# FlexEMG_v0r0_SF2-POWER.net
KiCad netlist of a schematic drawn in Altium Designer
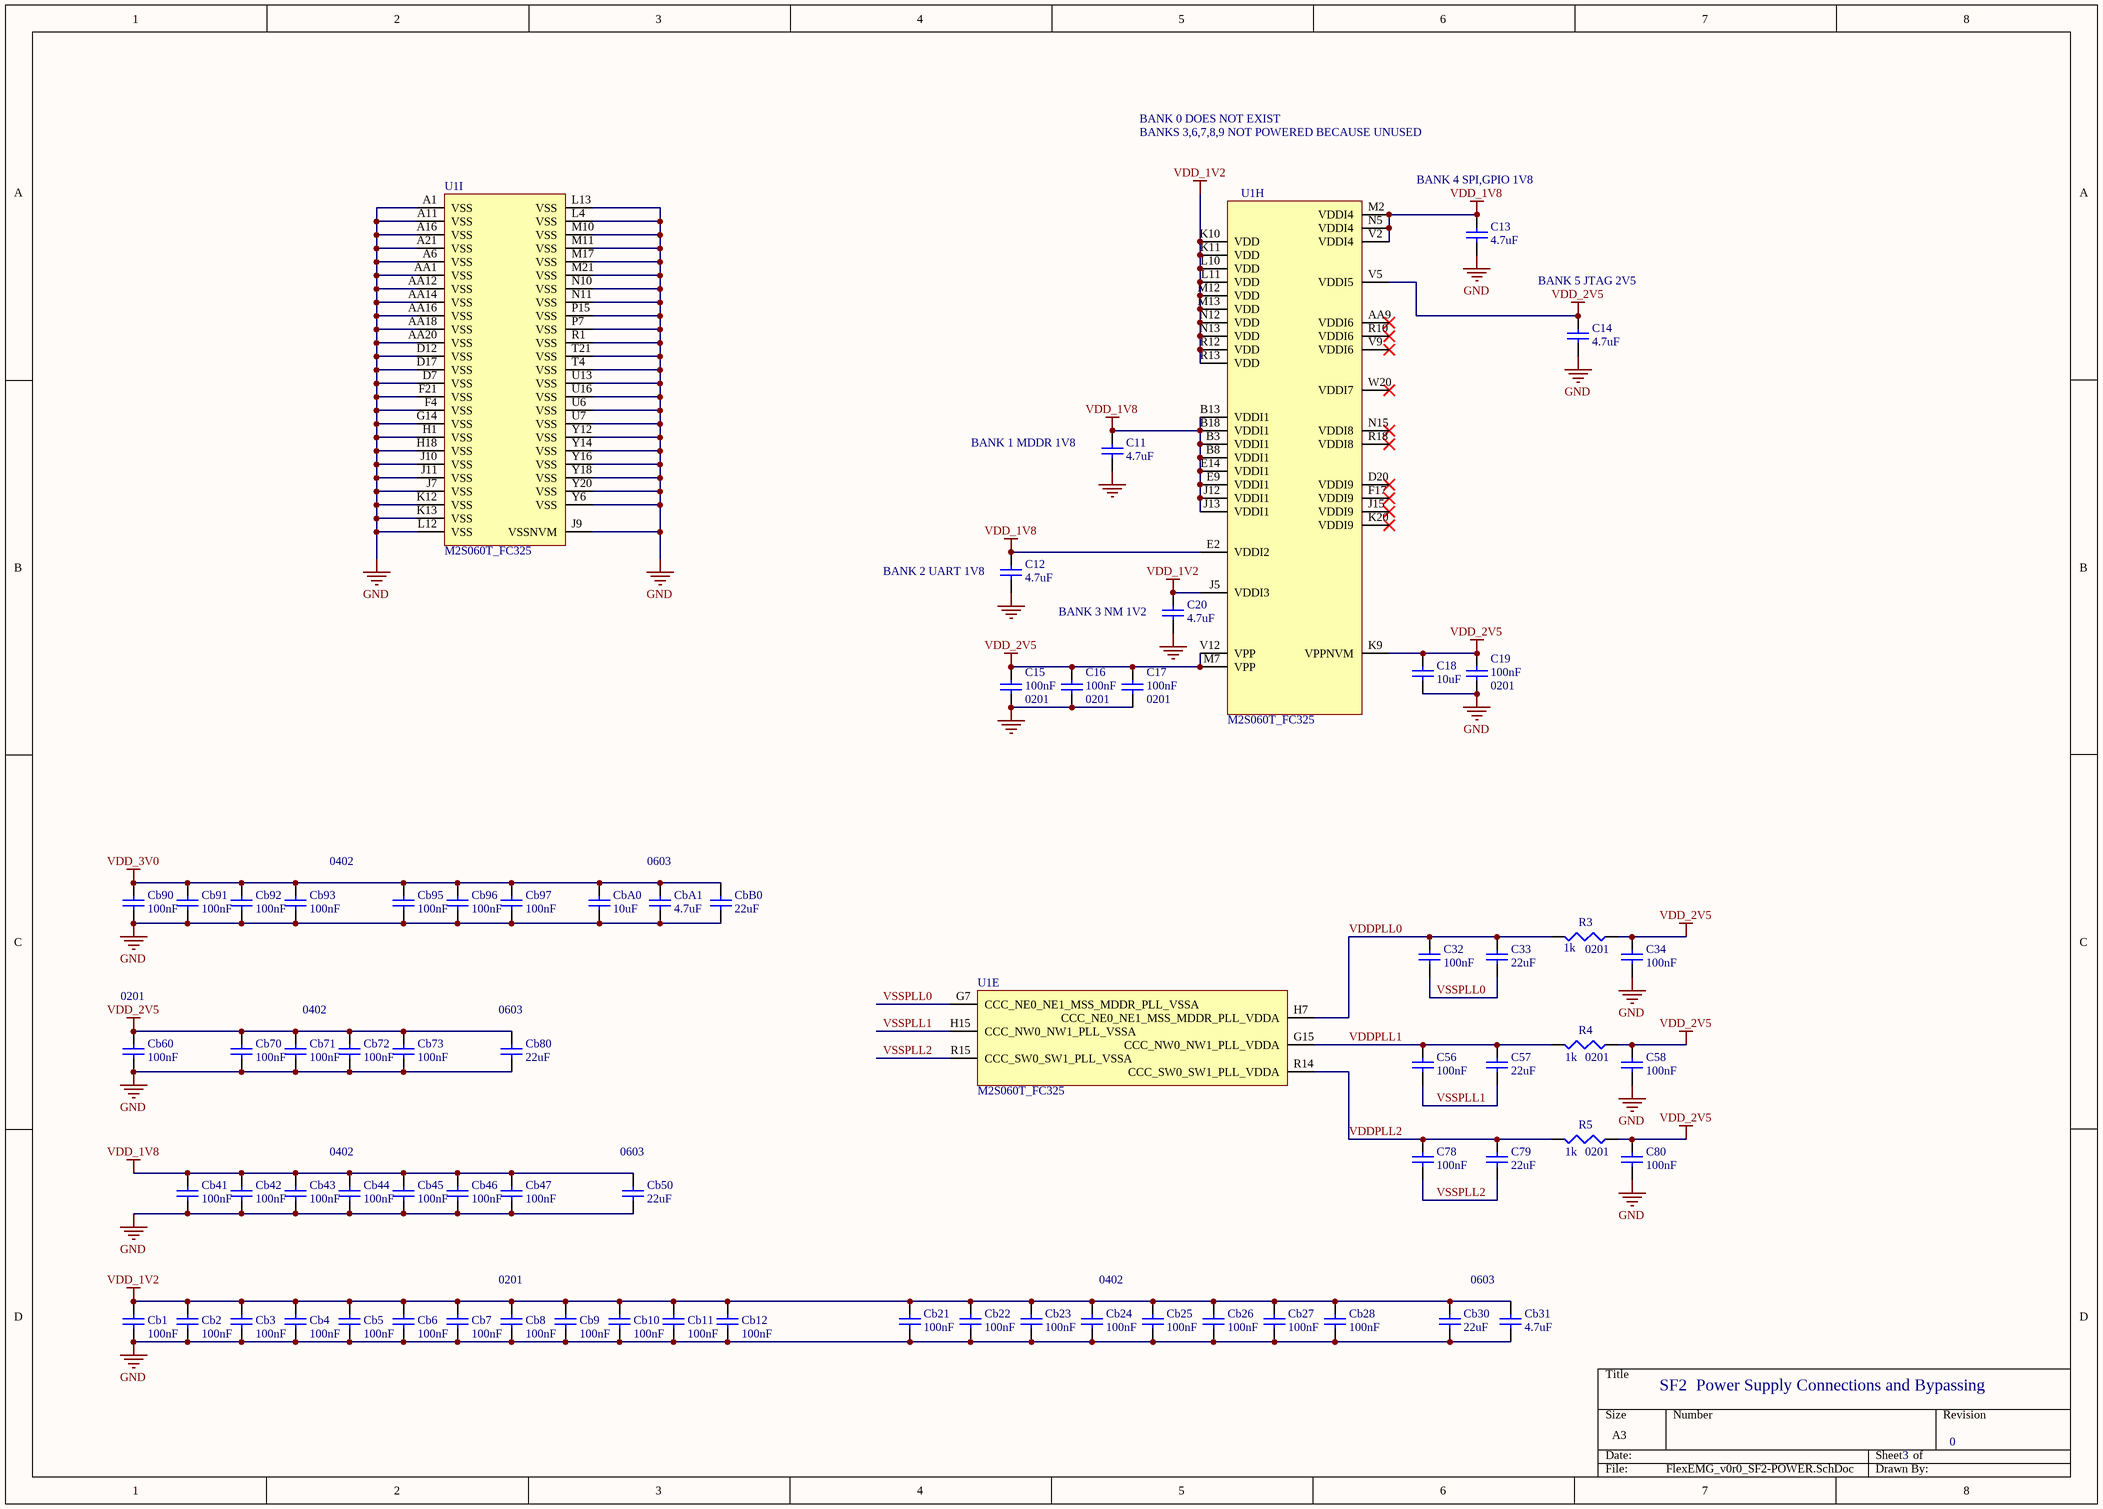
[diagram p0: FlexEMG_v0r0_SF2-POWER.SchDoc]

(export (version "E")
  (design (tool "Eeschema 10.0.6"))
  (components
    (comp (ref "C11")
      (value "4.7uF")
      (footprint "c0603-Murata-GR")
      (description "CAP CER 4.7UF 35V X5R 0603")
      (fields (field (name "MANUFACTURER") "Murata") (field (name "Comment") "GRM188R6YA475KE15D"))
      (libsource (lib "Custom") (part "Cap"))
    )
    (comp (ref "C12")
      (value "4.7uF")
      (footprint "c0603-Murata-GR")
      (description "CAP CER 4.7UF 35V X5R 0603")
      (fields (field (name "MANUFACTURER") "Murata") (field (name "Comment") "GRM188R6YA475KE15D"))
      (libsource (lib "Custom") (part "Cap"))
    )
    (comp (ref "C13")
      (value "4.7uF")
      (footprint "c0603-Murata-GR")
      (description "CAP CER 4.7UF 35V X5R 0603")
      (fields (field (name "MANUFACTURER") "Murata") (field (name "Comment") "GRM188R6YA475KE15D"))
      (libsource (lib "Custom") (part "Cap"))
    )
    (comp (ref "C14")
      (value "4.7uF")
      (footprint "c0603-Murata-GR")
      (description "CAP CER 4.7UF 35V X5R 0603")
      (fields (field (name "MANUFACTURER") "Murata") (field (name "Comment") "GRM188R6YA475KE15D"))
      (libsource (lib "Custom") (part "Cap"))
    )
    (comp (ref "C15")
      (value "100nF")
      (footprint "c0201-Murata-GR")
      (description "CAP CER 0.1UF 16V X7S 0201")
      (fields
        (field (name "MANUFACTURER") "Murata")
        (field (name "PACKAGE") "0201")
        (field (name "Comment") "GRM033R6YA104KE14D")
      )
      (libsource (lib "Custom") (part "Cap"))
    )
    (comp (ref "C16")
      (value "100nF")
      (footprint "c0201-Murata-GR")
      (description "CAP CER 0.1UF 16V X7S 0201")
      (fields
        (field (name "MANUFACTURER") "Murata")
        (field (name "PACKAGE") "0201")
        (field (name "Comment") "GRM033R6YA104KE14D")
      )
      (libsource (lib "Custom") (part "Cap"))
    )
    (comp (ref "C17")
      (value "100nF")
      (footprint "c0201-Murata-GR")
      (description "CAP CER 0.1UF 16V X7S 0201")
      (fields
        (field (name "MANUFACTURER") "Murata")
        (field (name "PACKAGE") "0201")
        (field (name "Comment") "GRM033R6YA104KE14D")
      )
      (libsource (lib "Custom") (part "Cap"))
    )
    (comp (ref "C18")
      (value "10uF")
      (footprint "c0603-Murata-GR")
      (description "CAP CER 10UF 25V X5R 0603 20%")
      (fields (field (name "MANUFACTURER") "Murata") (field (name "Comment") "GRM188R61E106MA73D"))
      (libsource (lib "Custom") (part "Cap"))
    )
    (comp (ref "C19")
      (value "100nF")
      (footprint "c0201-Murata-GR")
      (description "CAP CER 0.1UF 16V X7S 0201")
      (fields
        (field (name "MANUFACTURER") "Murata")
        (field (name "PACKAGE") "0201")
        (field (name "Comment") "GRM033R6YA104KE14D")
      )
      (libsource (lib "Custom") (part "Cap"))
    )
    (comp (ref "C20")
      (value "4.7uF")
      (footprint "c0603-Murata-GR")
      (description "CAP CER 4.7UF 35V X5R 0603")
      (fields (field (name "MANUFACTURER") "Murata") (field (name "Comment") "GRM188R6YA475KE15D"))
      (libsource (lib "Custom") (part "Cap"))
    )
    (comp (ref "C32")
      (value "100nF")
      (footprint "c0402-Murata-GR")
      (description "CAP CER 0.1UF 50V X5R 0402")
      (fields (field (name "MANUFACTURER") "Murata") (field (name "Comment") "GRM155R61H104KE19D"))
      (libsource (lib "Custom") (part "Cap"))
    )
    (comp (ref "C33")
      (value "22uF")
      (footprint "c0603-Murata-GR")
      (description "CAP CER 22UF 10V X5R 0603")
      (fields (field (name "MANUFACTURER") "Murata") (field (name "Comment") "GRM187R61A226ME15D"))
      (libsource (lib "Custom") (part "Cap"))
    )
    (comp (ref "C34")
      (value "100nF")
      (footprint "c0402-Murata-GR")
      (description "CAP CER 0.1UF 50V X5R 0402")
      (fields (field (name "MANUFACTURER") "Murata") (field (name "Comment") "GRM155R61H104KE19D"))
      (libsource (lib "Custom") (part "Cap"))
    )
    (comp (ref "C56")
      (value "100nF")
      (footprint "c0402-Murata-GR")
      (description "CAP CER 0.1UF 50V X5R 0402")
      (fields (field (name "MANUFACTURER") "Murata") (field (name "Comment") "GRM155R61H104KE19D"))
      (libsource (lib "Custom") (part "Cap"))
    )
    (comp (ref "C57")
      (value "22uF")
      (footprint "c0603-Murata-GR")
      (description "CAP CER 22UF 10V X5R 0603")
      (fields (field (name "MANUFACTURER") "Murata") (field (name "Comment") "GRM187R61A226ME15D"))
      (libsource (lib "Custom") (part "Cap"))
    )
    (comp (ref "C58")
      (value "100nF")
      (footprint "c0402-Murata-GR")
      (description "CAP CER 0.1UF 50V X5R 0402")
      (fields (field (name "MANUFACTURER") "Murata") (field (name "Comment") "GRM155R61H104KE19D"))
      (libsource (lib "Custom") (part "Cap"))
    )
    (comp (ref "C78")
      (value "100nF")
      (footprint "c0402-Murata-GR")
      (description "CAP CER 0.1UF 50V X5R 0402")
      (fields (field (name "MANUFACTURER") "Murata") (field (name "Comment") "GRM155R61H104KE19D"))
      (libsource (lib "Custom") (part "Cap"))
    )
    (comp (ref "C79")
      (value "22uF")
      (footprint "c0603-Murata-GR")
      (description "CAP CER 22UF 10V X5R 0603")
      (fields (field (name "MANUFACTURER") "Murata") (field (name "Comment") "GRM187R61A226ME15D"))
      (libsource (lib "Custom") (part "Cap"))
    )
    (comp (ref "C80")
      (value "100nF")
      (footprint "c0402-Murata-GR")
      (description "CAP CER 0.1UF 50V X5R 0402")
      (fields (field (name "MANUFACTURER") "Murata") (field (name "Comment") "GRM155R61H104KE19D"))
      (libsource (lib "Custom") (part "Cap"))
    )
    (comp (ref "Cb1")
      (value "100nF")
      (footprint "c0201-Murata-GR")
      (description "CAP CER 0.1UF 16V X7S 0201")
      (fields (field (name "MANUFACTURER") "Murata") (field (name "Comment") "GRM033R6YA104KE14D"))
      (libsource (lib "Custom") (part "Cap"))
    )
    (comp (ref "Cb2")
      (value "100nF")
      (footprint "c0201-Murata-GR")
      (description "CAP CER 0.1UF 16V X7S 0201")
      (fields (field (name "MANUFACTURER") "Murata") (field (name "Comment") "GRM033R6YA104KE14D"))
      (libsource (lib "Custom") (part "Cap"))
    )
    (comp (ref "Cb3")
      (value "100nF")
      (footprint "c0201-Murata-GR")
      (description "CAP CER 0.1UF 16V X7S 0201")
      (fields (field (name "MANUFACTURER") "Murata") (field (name "Comment") "GRM033R6YA104KE14D"))
      (libsource (lib "Custom") (part "Cap"))
    )
    (comp (ref "Cb4")
      (value "100nF")
      (footprint "c0201-Murata-GR")
      (description "CAP CER 0.1UF 16V X7S 0201")
      (fields (field (name "MANUFACTURER") "Murata") (field (name "Comment") "GRM033R6YA104KE14D"))
      (libsource (lib "Custom") (part "Cap"))
    )
    (comp (ref "Cb5")
      (value "100nF")
      (footprint "c0201-Murata-GR")
      (description "CAP CER 0.1UF 16V X7S 0201")
      (fields (field (name "MANUFACTURER") "Murata") (field (name "Comment") "GRM033R6YA104KE14D"))
      (libsource (lib "Custom") (part "Cap"))
    )
    (comp (ref "Cb6")
      (value "100nF")
      (footprint "c0201-Murata-GR")
      (description "CAP CER 0.1UF 16V X7S 0201")
      (fields (field (name "MANUFACTURER") "Murata") (field (name "Comment") "GRM033R6YA104KE14D"))
      (libsource (lib "Custom") (part "Cap"))
    )
    (comp (ref "Cb7")
      (value "100nF")
      (footprint "c0201-Murata-GR")
      (description "CAP CER 0.1UF 16V X7S 0201")
      (fields (field (name "MANUFACTURER") "Murata") (field (name "Comment") "GRM033R6YA104KE14D"))
      (libsource (lib "Custom") (part "Cap"))
    )
    (comp (ref "Cb8")
      (value "100nF")
      (footprint "c0201-Murata-GR")
      (description "CAP CER 0.1UF 16V X7S 0201")
      (fields (field (name "MANUFACTURER") "Murata") (field (name "Comment") "GRM033R6YA104KE14D"))
      (libsource (lib "Custom") (part "Cap"))
    )
    (comp (ref "Cb9")
      (value "100nF")
      (footprint "c0201-Murata-GR")
      (description "CAP CER 0.1UF 16V X7S 0201")
      (fields (field (name "MANUFACTURER") "Murata") (field (name "Comment") "GRM033R6YA104KE14D"))
      (libsource (lib "Custom") (part "Cap"))
    )
    (comp (ref "Cb10")
      (value "100nF")
      (footprint "c0201-Murata-GR")
      (description "CAP CER 0.1UF 16V X7S 0201")
      (fields (field (name "MANUFACTURER") "Murata") (field (name "Comment") "GRM033R6YA104KE14D"))
      (libsource (lib "Custom") (part "Cap"))
    )
    (comp (ref "Cb11")
      (value "100nF")
      (footprint "c0201-Murata-GR")
      (description "CAP CER 0.1UF 16V X7S 0201")
      (fields (field (name "MANUFACTURER") "Murata") (field (name "Comment") "GRM033R6YA104KE14D"))
      (libsource (lib "Custom") (part "Cap"))
    )
    (comp (ref "Cb12")
      (value "100nF")
      (footprint "c0201-Murata-GR")
      (description "CAP CER 0.1UF 16V X7S 0201")
      (fields (field (name "MANUFACTURER") "Murata") (field (name "Comment") "GRM033R6YA104KE14D"))
      (libsource (lib "Custom") (part "Cap"))
    )
    (comp (ref "Cb21")
      (value "100nF")
      (footprint "c0402-Murata-GR")
      (description "CAP CER 0.1UF 50V X5R 0402")
      (fields (field (name "MANUFACTURER") "Murata") (field (name "Comment") "GRM155R61H104KE19D"))
      (libsource (lib "Custom") (part "Cap"))
    )
    (comp (ref "Cb22")
      (value "100nF")
      (footprint "c0402-Murata-GR")
      (description "CAP CER 0.1UF 50V X5R 0402")
      (fields (field (name "MANUFACTURER") "Murata") (field (name "Comment") "GRM155R61H104KE19D"))
      (libsource (lib "Custom") (part "Cap"))
    )
    (comp (ref "Cb23")
      (value "100nF")
      (footprint "c0402-Murata-GR")
      (description "CAP CER 0.1UF 50V X5R 0402")
      (fields (field (name "MANUFACTURER") "Murata") (field (name "Comment") "GRM155R61H104KE19D"))
      (libsource (lib "Custom") (part "Cap"))
    )
    (comp (ref "Cb24")
      (value "100nF")
      (footprint "c0402-Murata-GR")
      (description "CAP CER 0.1UF 50V X5R 0402")
      (fields (field (name "MANUFACTURER") "Murata") (field (name "Comment") "GRM155R61H104KE19D"))
      (libsource (lib "Custom") (part "Cap"))
    )
    (comp (ref "Cb25")
      (value "100nF")
      (footprint "c0402-Murata-GR")
      (description "CAP CER 0.1UF 50V X5R 0402")
      (fields (field (name "MANUFACTURER") "Murata") (field (name "Comment") "GRM155R61H104KE19D"))
      (libsource (lib "Custom") (part "Cap"))
    )
    (comp (ref "Cb26")
      (value "100nF")
      (footprint "c0402-Murata-GR")
      (description "CAP CER 0.1UF 50V X5R 0402")
      (fields (field (name "MANUFACTURER") "Murata") (field (name "Comment") "GRM155R61H104KE19D"))
      (libsource (lib "Custom") (part "Cap"))
    )
    (comp (ref "Cb27")
      (value "100nF")
      (footprint "c0402-Murata-GR")
      (description "CAP CER 0.1UF 50V X5R 0402")
      (fields (field (name "MANUFACTURER") "Murata") (field (name "Comment") "GRM155R61H104KE19D"))
      (libsource (lib "Custom") (part "Cap"))
    )
    (comp (ref "Cb28")
      (value "100nF")
      (footprint "c0402-Murata-GR")
      (description "CAP CER 0.1UF 50V X5R 0402")
      (fields (field (name "MANUFACTURER") "Murata") (field (name "Comment") "GRM155R61H104KE19D"))
      (libsource (lib "Custom") (part "Cap"))
    )
    (comp (ref "Cb30")
      (value "22uF")
      (footprint "c0603-Murata-GR")
      (description "CAP CER 22UF 10V X5R 0603")
      (fields (field (name "MANUFACTURER") "Murata") (field (name "Comment") "GRM187R61A226ME15D"))
      (libsource (lib "Custom") (part "Cap"))
    )
    (comp (ref "Cb31")
      (value "4.7uF")
      (footprint "c0603-Murata-GR")
      (description "CAP CER 4.7UF 35V X5R 0603")
      (fields (field (name "MANUFACTURER") "Murata") (field (name "Comment") "GRM188R6YA475KE15D"))
      (libsource (lib "Custom") (part "Cap"))
    )
    (comp (ref "Cb41")
      (value "100nF")
      (footprint "c0402-Murata-GR")
      (description "CAP CER 0.1UF 50V X5R 0402")
      (fields (field (name "MANUFACTURER") "Murata") (field (name "Comment") "GRM155R61H104KE19D"))
      (libsource (lib "Custom") (part "Cap"))
    )
    (comp (ref "Cb42")
      (value "100nF")
      (footprint "c0402-Murata-GR")
      (description "CAP CER 0.1UF 50V X5R 0402")
      (fields (field (name "MANUFACTURER") "Murata") (field (name "Comment") "GRM155R61H104KE19D"))
      (libsource (lib "Custom") (part "Cap"))
    )
    (comp (ref "Cb43")
      (value "100nF")
      (footprint "c0402-Murata-GR")
      (description "CAP CER 0.1UF 50V X5R 0402")
      (fields (field (name "MANUFACTURER") "Murata") (field (name "Comment") "GRM155R61H104KE19D"))
      (libsource (lib "Custom") (part "Cap"))
    )
    (comp (ref "Cb44")
      (value "100nF")
      (footprint "c0402-Murata-GR")
      (description "CAP CER 0.1UF 50V X5R 0402")
      (fields (field (name "MANUFACTURER") "Murata") (field (name "Comment") "GRM155R61H104KE19D"))
      (libsource (lib "Custom") (part "Cap"))
    )
    (comp (ref "Cb45")
      (value "100nF")
      (footprint "c0402-Murata-GR")
      (description "CAP CER 0.1UF 50V X5R 0402")
      (fields (field (name "MANUFACTURER") "Murata") (field (name "Comment") "GRM155R61H104KE19D"))
      (libsource (lib "Custom") (part "Cap"))
    )
    (comp (ref "Cb46")
      (value "100nF")
      (footprint "c0402-Murata-GR")
      (description "CAP CER 0.1UF 50V X5R 0402")
      (fields (field (name "MANUFACTURER") "Murata") (field (name "Comment") "GRM155R61H104KE19D"))
      (libsource (lib "Custom") (part "Cap"))
    )
    (comp (ref "Cb47")
      (value "100nF")
      (footprint "c0402-Murata-GR")
      (description "CAP CER 0.1UF 50V X5R 0402")
      (fields (field (name "MANUFACTURER") "Murata") (field (name "Comment") "GRM155R61H104KE19D"))
      (libsource (lib "Custom") (part "Cap"))
    )
    (comp (ref "Cb50")
      (value "22uF")
      (footprint "c0603-Murata-GR")
      (description "CAP CER 22UF 10V X5R 0603")
      (fields (field (name "MANUFACTURER") "Murata") (field (name "Comment") "GRM187R61A226ME15D"))
      (libsource (lib "Custom") (part "Cap"))
    )
    (comp (ref "Cb60")
      (value "100nF")
      (footprint "c0201-Murata-GR")
      (description "CAP CER 0.1UF 16V X7S 0201")
      (fields (field (name "MANUFACTURER") "Murata") (field (name "Comment") "GRM033R6YA104KE14D"))
      (libsource (lib "Custom") (part "Cap"))
    )
    (comp (ref "Cb70")
      (value "100nF")
      (footprint "c0402-Murata-GR")
      (description "CAP CER 0.1UF 50V X5R 0402")
      (fields (field (name "MANUFACTURER") "Murata") (field (name "Comment") "GRM155R61H104KE19D"))
      (libsource (lib "Custom") (part "Cap"))
    )
    (comp (ref "Cb71")
      (value "100nF")
      (footprint "c0402-Murata-GR")
      (description "CAP CER 0.1UF 50V X5R 0402")
      (fields (field (name "MANUFACTURER") "Murata") (field (name "Comment") "GRM155R61H104KE19D"))
      (libsource (lib "Custom") (part "Cap"))
    )
    (comp (ref "Cb72")
      (value "100nF")
      (footprint "c0402-Murata-GR")
      (description "CAP CER 0.1UF 50V X5R 0402")
      (fields (field (name "MANUFACTURER") "Murata") (field (name "Comment") "GRM155R61H104KE19D"))
      (libsource (lib "Custom") (part "Cap"))
    )
    (comp (ref "Cb73")
      (value "100nF")
      (footprint "c0402-Murata-GR")
      (description "CAP CER 0.1UF 50V X5R 0402")
      (fields (field (name "MANUFACTURER") "Murata") (field (name "Comment") "GRM155R61H104KE19D"))
      (libsource (lib "Custom") (part "Cap"))
    )
    (comp (ref "Cb80")
      (value "22uF")
      (footprint "c0603-Murata-GR")
      (description "CAP CER 22UF 10V X5R 0603")
      (fields (field (name "MANUFACTURER") "Murata") (field (name "Comment") "GRM187R61A226ME15D"))
      (libsource (lib "Custom") (part "Cap"))
    )
    (comp (ref "Cb90")
      (value "100nF")
      (footprint "c0402-Murata-GR")
      (description "CAP CER 0.1UF 50V X5R 0402")
      (fields (field (name "MANUFACTURER") "Murata") (field (name "Comment") "GRM155R61H104KE19D"))
      (libsource (lib "Custom") (part "Cap"))
    )
    (comp (ref "Cb91")
      (value "100nF")
      (footprint "c0402-Murata-GR")
      (description "CAP CER 0.1UF 50V X5R 0402")
      (fields (field (name "MANUFACTURER") "Murata") (field (name "Comment") "GRM155R61H104KE19D"))
      (libsource (lib "Custom") (part "Cap"))
    )
    (comp (ref "Cb92")
      (value "100nF")
      (footprint "c0402-Murata-GR")
      (description "CAP CER 0.1UF 50V X5R 0402")
      (fields (field (name "MANUFACTURER") "Murata") (field (name "Comment") "GRM155R61H104KE19D"))
      (libsource (lib "Custom") (part "Cap"))
    )
    (comp (ref "Cb93")
      (value "100nF")
      (footprint "c0402-Murata-GR")
      (description "CAP CER 0.1UF 50V X5R 0402")
      (fields (field (name "MANUFACTURER") "Murata") (field (name "Comment") "GRM155R61H104KE19D"))
      (libsource (lib "Custom") (part "Cap"))
    )
    (comp (ref "Cb95")
      (value "100nF")
      (footprint "c0402-Murata-GR")
      (description "CAP CER 0.1UF 50V X5R 0402")
      (fields (field (name "MANUFACTURER") "Murata") (field (name "Comment") "GRM155R61H104KE19D"))
      (libsource (lib "Custom") (part "Cap"))
    )
    (comp (ref "Cb96")
      (value "100nF")
      (footprint "c0402-Murata-GR")
      (description "CAP CER 0.1UF 50V X5R 0402")
      (fields (field (name "MANUFACTURER") "Murata") (field (name "Comment") "GRM155R61H104KE19D"))
      (libsource (lib "Custom") (part "Cap"))
    )
    (comp (ref "Cb97")
      (value "100nF")
      (footprint "c0402-Murata-GR")
      (description "CAP CER 0.1UF 50V X5R 0402")
      (fields (field (name "MANUFACTURER") "Murata") (field (name "Comment") "GRM155R61H104KE19D"))
      (libsource (lib "Custom") (part "Cap"))
    )
    (comp (ref "CbA0")
      (value "10uF")
      (footprint "c0603-Murata-GR")
      (description "CAP CER 10UF 25V X5R 0603 20%")
      (fields (field (name "MANUFACTURER") "Murata") (field (name "Comment") "GRM188R61E106MA73D"))
      (libsource (lib "Custom") (part "Cap"))
    )
    (comp (ref "CbA1")
      (value "4.7uF")
      (footprint "c0603-Murata-GR")
      (description "CAP CER 4.7UF 35V X5R 0603")
      (fields (field (name "MANUFACTURER") "Murata") (field (name "Comment") "GRM188R6YA475KE15D"))
      (libsource (lib "Custom") (part "Cap"))
    )
    (comp (ref "CbB0")
      (value "22uF")
      (footprint "c0603-Murata-GR")
      (description "CAP CER 22UF 10V X5R 0603")
      (fields (field (name "MANUFACTURER") "Murata") (field (name "Comment") "GRM187R61A226ME15D"))
      (libsource (lib "Custom") (part "Cap"))
    )
    (comp (ref "R3")
      (value "1k")
      (footprint "0201_p")
      (description "RES SMD 1K OHM 1% 1/20W 0201")
      (fields
        (field (name "MANUFACTURER") "Panasonic")
        (field (name "POWER") "1/20W")
        (field (name "PACKAGE") "0201")
      )
      (libsource (lib "Custom") (part "Resistor"))
    )
    (comp (ref "R4")
      (value "1k")
      (footprint "0201_p")
      (description "RES SMD 1K OHM 1% 1/20W 0201")
      (fields
        (field (name "MANUFACTURER") "Panasonic")
        (field (name "POWER") "1/20W")
        (field (name "PACKAGE") "0201")
      )
      (libsource (lib "Custom") (part "Resistor"))
    )
    (comp (ref "R5")
      (value "1k")
      (footprint "0201_p")
      (description "RES SMD 1K OHM 1% 1/20W 0201")
      (fields
        (field (name "MANUFACTURER") "Panasonic")
        (field (name "POWER") "1/20W")
        (field (name "PACKAGE") "0201")
      )
      (libsource (lib "Custom") (part "Resistor"))
    )
    (comp (ref "U1")
      (value "M2S060T_FC325")
      (footprint "MCSM-CS-325")
      (description "SmartFusion2")
      (fields (field (name "MANUFACTURER") "Microsemi"))
      (libsource (lib "CM") (part "M2S060T_FC325"))
    )
  )
  (nets
    (net (code "1") (name "/VDDPLL0") (class "Default")
      (node (ref "C32") (pin "2") (pinfunction "2_2") (pintype "passive"))
      (node (ref "C33") (pin "2") (pinfunction "2_2") (pintype "passive"))
      (node (ref "R3") (pin "2") (pinfunction "2_2") (pintype "passive"))
      (node (ref "U1") (pin "H7") (pinfunction "CCC_NE0_NE1_MSS_MDDR_PLL_VDDA_H7") (pintype "power_in"))
    )
    (net (code "2") (name "/VDDPLL1") (class "Default")
      (node (ref "C56") (pin "2") (pinfunction "2_2") (pintype "passive"))
      (node (ref "C57") (pin "2") (pinfunction "2_2") (pintype "passive"))
      (node (ref "R4") (pin "2") (pinfunction "2_2") (pintype "passive"))
      (node (ref "U1") (pin "G15") (pinfunction "CCC_NW0_NW1_PLL_VDDA_G15") (pintype "power_in"))
    )
    (net (code "3") (name "/VDDPLL2") (class "Default")
      (node (ref "C78") (pin "2") (pinfunction "2_2") (pintype "passive"))
      (node (ref "C79") (pin "2") (pinfunction "2_2") (pintype "passive"))
      (node (ref "R5") (pin "2") (pinfunction "2_2") (pintype "passive"))
      (node (ref "U1") (pin "R14") (pinfunction "CCC_SW0_SW1_PLL_VDDA_R14") (pintype "power_in"))
    )
    (net (code "4") (name "/VSSPLL0") (class "Default")
      (node (ref "C32") (pin "1") (pinfunction "1_1") (pintype "passive"))
      (node (ref "C33") (pin "1") (pinfunction "1_1") (pintype "passive"))
      (node (ref "U1") (pin "G7") (pinfunction "CCC_NE0_NE1_MSS_MDDR_PLL_VSSA_G7") (pintype "power_in"))
    )
    (net (code "5") (name "/VSSPLL1") (class "Default")
      (node (ref "C56") (pin "1") (pinfunction "1_1") (pintype "passive"))
      (node (ref "C57") (pin "1") (pinfunction "1_1") (pintype "passive"))
      (node (ref "U1") (pin "H15") (pinfunction "CCC_NW0_NW1_PLL_VSSA_H15") (pintype "power_in"))
    )
    (net (code "6") (name "/VSSPLL2") (class "Default")
      (node (ref "C78") (pin "1") (pinfunction "1_1") (pintype "passive"))
      (node (ref "C79") (pin "1") (pinfunction "1_1") (pintype "passive"))
      (node (ref "U1") (pin "R15") (pinfunction "CCC_SW0_SW1_PLL_VSSA_R15") (pintype "power_in"))
    )
    (net (code "7") (name "GND") (class "Default")
      (node (ref "C11") (pin "1") (pinfunction "1_1") (pintype "passive"))
      (node (ref "C12") (pin "1") (pinfunction "1_1") (pintype "passive"))
      (node (ref "C13") (pin "1") (pinfunction "1_1") (pintype "passive"))
      (node (ref "C14") (pin "1") (pinfunction "1_1") (pintype "passive"))
      (node (ref "C15") (pin "1") (pinfunction "1_1") (pintype "passive"))
      (node (ref "C16") (pin "1") (pinfunction "1_1") (pintype "passive"))
      (node (ref "C17") (pin "1") (pinfunction "1_1") (pintype "passive"))
      (node (ref "C18") (pin "1") (pinfunction "1_1") (pintype "passive"))
      (node (ref "C19") (pin "1") (pinfunction "1_1") (pintype "passive"))
      (node (ref "C20") (pin "1") (pinfunction "1_1") (pintype "passive"))
      (node (ref "C34") (pin "1") (pinfunction "1_1") (pintype "passive"))
      (node (ref "C58") (pin "1") (pinfunction "1_1") (pintype "passive"))
      (node (ref "C80") (pin "1") (pinfunction "1_1") (pintype "passive"))
      (node (ref "Cb1") (pin "1") (pinfunction "1_1") (pintype "passive"))
      (node (ref "Cb10") (pin "1") (pinfunction "1_1") (pintype "passive"))
      (node (ref "Cb11") (pin "1") (pinfunction "1_1") (pintype "passive"))
      (node (ref "Cb12") (pin "1") (pinfunction "1_1") (pintype "passive"))
      (node (ref "Cb2") (pin "1") (pinfunction "1_1") (pintype "passive"))
      (node (ref "Cb21") (pin "1") (pinfunction "1_1") (pintype "passive"))
      (node (ref "Cb22") (pin "1") (pinfunction "1_1") (pintype "passive"))
      (node (ref "Cb23") (pin "1") (pinfunction "1_1") (pintype "passive"))
      (node (ref "Cb24") (pin "1") (pinfunction "1_1") (pintype "passive"))
      (node (ref "Cb25") (pin "1") (pinfunction "1_1") (pintype "passive"))
      (node (ref "Cb26") (pin "1") (pinfunction "1_1") (pintype "passive"))
      (node (ref "Cb27") (pin "1") (pinfunction "1_1") (pintype "passive"))
      (node (ref "Cb28") (pin "1") (pinfunction "1_1") (pintype "passive"))
      (node (ref "Cb3") (pin "1") (pinfunction "1_1") (pintype "passive"))
      (node (ref "Cb30") (pin "1") (pinfunction "1_1") (pintype "passive"))
      (node (ref "Cb31") (pin "1") (pinfunction "1_1") (pintype "passive"))
      (node (ref "Cb4") (pin "1") (pinfunction "1_1") (pintype "passive"))
      (node (ref "Cb41") (pin "1") (pinfunction "1_1") (pintype "passive"))
      (node (ref "Cb42") (pin "1") (pinfunction "1_1") (pintype "passive"))
      (node (ref "Cb43") (pin "1") (pinfunction "1_1") (pintype "passive"))
      (node (ref "Cb44") (pin "1") (pinfunction "1_1") (pintype "passive"))
      (node (ref "Cb45") (pin "1") (pinfunction "1_1") (pintype "passive"))
      (node (ref "Cb46") (pin "1") (pinfunction "1_1") (pintype "passive"))
      (node (ref "Cb47") (pin "1") (pinfunction "1_1") (pintype "passive"))
      (node (ref "Cb5") (pin "1") (pinfunction "1_1") (pintype "passive"))
      (node (ref "Cb50") (pin "1") (pinfunction "1_1") (pintype "passive"))
      (node (ref "Cb6") (pin "1") (pinfunction "1_1") (pintype "passive"))
      (node (ref "Cb60") (pin "1") (pinfunction "1_1") (pintype "passive"))
      (node (ref "Cb7") (pin "1") (pinfunction "1_1") (pintype "passive"))
      (node (ref "Cb70") (pin "1") (pinfunction "1_1") (pintype "passive"))
      (node (ref "Cb71") (pin "1") (pinfunction "1_1") (pintype "passive"))
      (node (ref "Cb72") (pin "1") (pinfunction "1_1") (pintype "passive"))
      (node (ref "Cb73") (pin "1") (pinfunction "1_1") (pintype "passive"))
      (node (ref "Cb8") (pin "1") (pinfunction "1_1") (pintype "passive"))
      (node (ref "Cb80") (pin "1") (pinfunction "1_1") (pintype "passive"))
      (node (ref "Cb9") (pin "1") (pinfunction "1_1") (pintype "passive"))
      (node (ref "Cb90") (pin "1") (pinfunction "1_1") (pintype "passive"))
      (node (ref "Cb91") (pin "1") (pinfunction "1_1") (pintype "passive"))
      (node (ref "Cb92") (pin "1") (pinfunction "1_1") (pintype "passive"))
      (node (ref "Cb93") (pin "1") (pinfunction "1_1") (pintype "passive"))
      (node (ref "Cb95") (pin "1") (pinfunction "1_1") (pintype "passive"))
      (node (ref "Cb96") (pin "1") (pinfunction "1_1") (pintype "passive"))
      (node (ref "Cb97") (pin "1") (pinfunction "1_1") (pintype "passive"))
      (node (ref "CbA0") (pin "1") (pinfunction "1_1") (pintype "passive"))
      (node (ref "CbA1") (pin "1") (pinfunction "1_1") (pintype "passive"))
      (node (ref "CbB0") (pin "1") (pinfunction "1_1") (pintype "passive"))
      (node (ref "U1") (pin "A1") (pinfunction "VSS_A1") (pintype "power_in"))
      (node (ref "U1") (pin "A11") (pinfunction "VSS_A11") (pintype "power_in"))
      (node (ref "U1") (pin "A16") (pinfunction "VSS_A16") (pintype "power_in"))
      (node (ref "U1") (pin "A21") (pinfunction "VSS_A21") (pintype "power_in"))
      (node (ref "U1") (pin "A6") (pinfunction "VSS_A6") (pintype "power_in"))
      (node (ref "U1") (pin "AA1") (pinfunction "VSS_AA1") (pintype "power_in"))
      (node (ref "U1") (pin "AA12") (pinfunction "VSS_AA12") (pintype "power_in"))
      (node (ref "U1") (pin "AA14") (pinfunction "VSS_AA14") (pintype "power_in"))
      (node (ref "U1") (pin "AA16") (pinfunction "VSS_AA16") (pintype "power_in"))
      (node (ref "U1") (pin "AA18") (pinfunction "VSS_AA18") (pintype "power_in"))
      (node (ref "U1") (pin "AA20") (pinfunction "VSS_AA20") (pintype "power_in"))
      (node (ref "U1") (pin "D12") (pinfunction "VSS_D12") (pintype "power_in"))
      (node (ref "U1") (pin "D17") (pinfunction "VSS_D17") (pintype "power_in"))
      (node (ref "U1") (pin "D7") (pinfunction "VSS_D7") (pintype "power_in"))
      (node (ref "U1") (pin "F21") (pinfunction "VSS_F21") (pintype "power_in"))
      (node (ref "U1") (pin "F4") (pinfunction "VSS_F4") (pintype "power_in"))
      (node (ref "U1") (pin "G14") (pinfunction "VSS_G14") (pintype "power_in"))
      (node (ref "U1") (pin "H1") (pinfunction "VSS_H1") (pintype "power_in"))
      (node (ref "U1") (pin "H18") (pinfunction "VSS_H18") (pintype "power_in"))
      (node (ref "U1") (pin "J10") (pinfunction "VSS_J10") (pintype "power_in"))
      (node (ref "U1") (pin "J11") (pinfunction "VSS_J11") (pintype "power_in"))
      (node (ref "U1") (pin "J7") (pinfunction "VSS_J7") (pintype "power_in"))
      (node (ref "U1") (pin "J9") (pinfunction "VSSNVM_J9") (pintype "power_in"))
      (node (ref "U1") (pin "K12") (pinfunction "VSS_K12") (pintype "power_in"))
      (node (ref "U1") (pin "K13") (pinfunction "VSS_K13") (pintype "power_in"))
      (node (ref "U1") (pin "L12") (pinfunction "VSS_L12") (pintype "power_in"))
      (node (ref "U1") (pin "L13") (pinfunction "VSS_L13") (pintype "power_in"))
      (node (ref "U1") (pin "L4") (pinfunction "VSS_L4") (pintype "power_in"))
      (node (ref "U1") (pin "M10") (pinfunction "VSS_M10") (pintype "power_in"))
      (node (ref "U1") (pin "M11") (pinfunction "VSS_M11") (pintype "power_in"))
      (node (ref "U1") (pin "M17") (pinfunction "VSS_M17") (pintype "power_in"))
      (node (ref "U1") (pin "M21") (pinfunction "VSS_M21") (pintype "power_in"))
      (node (ref "U1") (pin "N10") (pinfunction "VSS_N10") (pintype "power_in"))
      (node (ref "U1") (pin "N11") (pinfunction "VSS_N11") (pintype "power_in"))
      (node (ref "U1") (pin "P15") (pinfunction "VSS_P15") (pintype "power_in"))
      (node (ref "U1") (pin "P7") (pinfunction "VSS_P7") (pintype "power_in"))
      (node (ref "U1") (pin "R1") (pinfunction "VSS_R1") (pintype "power_in"))
      (node (ref "U1") (pin "T21") (pinfunction "VSS_T21") (pintype "power_in"))
      (node (ref "U1") (pin "T4") (pinfunction "VSS_T4") (pintype "power_in"))
      (node (ref "U1") (pin "U13") (pinfunction "VSS_U13") (pintype "power_in"))
      (node (ref "U1") (pin "U16") (pinfunction "VSS_U16") (pintype "power_in"))
      (node (ref "U1") (pin "U6") (pinfunction "VSS_U6") (pintype "power_in"))
      (node (ref "U1") (pin "U7") (pinfunction "VSS_U7") (pintype "power_in"))
      (node (ref "U1") (pin "Y12") (pinfunction "VSS_Y12") (pintype "power_in"))
      (node (ref "U1") (pin "Y14") (pinfunction "VSS_Y14") (pintype "power_in"))
      (node (ref "U1") (pin "Y16") (pinfunction "VSS_Y16") (pintype "power_in"))
      (node (ref "U1") (pin "Y18") (pinfunction "VSS_Y18") (pintype "power_in"))
      (node (ref "U1") (pin "Y20") (pinfunction "VSS_Y20") (pintype "power_in"))
      (node (ref "U1") (pin "Y6") (pinfunction "VSS_Y6") (pintype "power_in"))
    )
    (net (code "8") (name "VDD_1V2") (class "Default")
      (node (ref "C20") (pin "2") (pinfunction "2_2") (pintype "passive"))
      (node (ref "Cb1") (pin "2") (pinfunction "2_2") (pintype "passive"))
      (node (ref "Cb10") (pin "2") (pinfunction "2_2") (pintype "passive"))
      (node (ref "Cb11") (pin "2") (pinfunction "2_2") (pintype "passive"))
      (node (ref "Cb12") (pin "2") (pinfunction "2_2") (pintype "passive"))
      (node (ref "Cb2") (pin "2") (pinfunction "2_2") (pintype "passive"))
      (node (ref "Cb21") (pin "2") (pinfunction "2_2") (pintype "passive"))
      (node (ref "Cb22") (pin "2") (pinfunction "2_2") (pintype "passive"))
      (node (ref "Cb23") (pin "2") (pinfunction "2_2") (pintype "passive"))
      (node (ref "Cb24") (pin "2") (pinfunction "2_2") (pintype "passive"))
      (node (ref "Cb25") (pin "2") (pinfunction "2_2") (pintype "passive"))
      (node (ref "Cb26") (pin "2") (pinfunction "2_2") (pintype "passive"))
      (node (ref "Cb27") (pin "2") (pinfunction "2_2") (pintype "passive"))
      (node (ref "Cb28") (pin "2") (pinfunction "2_2") (pintype "passive"))
      (node (ref "Cb3") (pin "2") (pinfunction "2_2") (pintype "passive"))
      (node (ref "Cb30") (pin "2") (pinfunction "2_2") (pintype "passive"))
      (node (ref "Cb31") (pin "2") (pinfunction "2_2") (pintype "passive"))
      (node (ref "Cb4") (pin "2") (pinfunction "2_2") (pintype "passive"))
      (node (ref "Cb5") (pin "2") (pinfunction "2_2") (pintype "passive"))
      (node (ref "Cb6") (pin "2") (pinfunction "2_2") (pintype "passive"))
      (node (ref "Cb7") (pin "2") (pinfunction "2_2") (pintype "passive"))
      (node (ref "Cb8") (pin "2") (pinfunction "2_2") (pintype "passive"))
      (node (ref "Cb9") (pin "2") (pinfunction "2_2") (pintype "passive"))
      (node (ref "U1") (pin "J5") (pinfunction "VDDI3_J5") (pintype "power_in"))
      (node (ref "U1") (pin "K10") (pinfunction "VDD_K10") (pintype "power_in"))
      (node (ref "U1") (pin "K11") (pinfunction "VDD_K11") (pintype "power_in"))
      (node (ref "U1") (pin "L10") (pinfunction "VDD_L10") (pintype "power_in"))
      (node (ref "U1") (pin "L11") (pinfunction "VDD_L11") (pintype "power_in"))
      (node (ref "U1") (pin "M12") (pinfunction "VDD_M12") (pintype "power_in"))
      (node (ref "U1") (pin "M13") (pinfunction "VDD_M13") (pintype "power_in"))
      (node (ref "U1") (pin "N12") (pinfunction "VDD_N12") (pintype "power_in"))
      (node (ref "U1") (pin "N13") (pinfunction "VDD_N13") (pintype "power_in"))
      (node (ref "U1") (pin "R12") (pinfunction "VDD_R12") (pintype "power_in"))
      (node (ref "U1") (pin "R13") (pinfunction "VDD_R13") (pintype "power_in"))
    )
    (net (code "9") (name "VDD_1V8") (class "Default")
      (node (ref "C11") (pin "2") (pinfunction "2_2") (pintype "passive"))
      (node (ref "C12") (pin "2") (pinfunction "2_2") (pintype "passive"))
      (node (ref "C13") (pin "2") (pinfunction "2_2") (pintype "passive"))
      (node (ref "Cb41") (pin "2") (pinfunction "2_2") (pintype "passive"))
      (node (ref "Cb42") (pin "2") (pinfunction "2_2") (pintype "passive"))
      (node (ref "Cb43") (pin "2") (pinfunction "2_2") (pintype "passive"))
      (node (ref "Cb44") (pin "2") (pinfunction "2_2") (pintype "passive"))
      (node (ref "Cb45") (pin "2") (pinfunction "2_2") (pintype "passive"))
      (node (ref "Cb46") (pin "2") (pinfunction "2_2") (pintype "passive"))
      (node (ref "Cb47") (pin "2") (pinfunction "2_2") (pintype "passive"))
      (node (ref "Cb50") (pin "2") (pinfunction "2_2") (pintype "passive"))
      (node (ref "U1") (pin "B13") (pinfunction "VDDI1_B13") (pintype "passive"))
      (node (ref "U1") (pin "B18") (pinfunction "VDDI1_B18") (pintype "passive"))
      (node (ref "U1") (pin "B3") (pinfunction "VDDI1_B3") (pintype "passive"))
      (node (ref "U1") (pin "B8") (pinfunction "VDDI1_B8") (pintype "passive"))
      (node (ref "U1") (pin "E14") (pinfunction "VDDI1_E14") (pintype "passive"))
      (node (ref "U1") (pin "E2") (pinfunction "VDDI2_E2") (pintype "power_in"))
      (node (ref "U1") (pin "E9") (pinfunction "VDDI1_E9") (pintype "passive"))
      (node (ref "U1") (pin "J12") (pinfunction "VDDI1_J12") (pintype "passive"))
      (node (ref "U1") (pin "J13") (pinfunction "VDDI1_J13") (pintype "passive"))
      (node (ref "U1") (pin "M2") (pinfunction "VDDI4_M2") (pintype "power_in"))
      (node (ref "U1") (pin "N5") (pinfunction "VDDI4_N5") (pintype "power_in"))
      (node (ref "U1") (pin "V2") (pinfunction "VDDI4_V2") (pintype "power_in"))
    )
    (net (code "10") (name "VDD_2V5") (class "Default")
      (node (ref "C14") (pin "2") (pinfunction "2_2") (pintype "passive"))
      (node (ref "C15") (pin "2") (pinfunction "2_2") (pintype "passive"))
      (node (ref "C16") (pin "2") (pinfunction "2_2") (pintype "passive"))
      (node (ref "C17") (pin "2") (pinfunction "2_2") (pintype "passive"))
      (node (ref "C18") (pin "2") (pinfunction "2_2") (pintype "passive"))
      (node (ref "C19") (pin "2") (pinfunction "2_2") (pintype "passive"))
      (node (ref "C34") (pin "2") (pinfunction "2_2") (pintype "passive"))
      (node (ref "C58") (pin "2") (pinfunction "2_2") (pintype "passive"))
      (node (ref "C80") (pin "2") (pinfunction "2_2") (pintype "passive"))
      (node (ref "Cb60") (pin "2") (pinfunction "2_2") (pintype "passive"))
      (node (ref "Cb70") (pin "2") (pinfunction "2_2") (pintype "passive"))
      (node (ref "Cb71") (pin "2") (pinfunction "2_2") (pintype "passive"))
      (node (ref "Cb72") (pin "2") (pinfunction "2_2") (pintype "passive"))
      (node (ref "Cb73") (pin "2") (pinfunction "2_2") (pintype "passive"))
      (node (ref "Cb80") (pin "2") (pinfunction "2_2") (pintype "passive"))
      (node (ref "R3") (pin "1") (pinfunction "1_1") (pintype "passive"))
      (node (ref "R4") (pin "1") (pinfunction "1_1") (pintype "passive"))
      (node (ref "R5") (pin "1") (pinfunction "1_1") (pintype "passive"))
      (node (ref "U1") (pin "K9") (pinfunction "VPPNVM_K9") (pintype "power_in"))
      (node (ref "U1") (pin "M7") (pinfunction "VPP_M7") (pintype "power_in"))
      (node (ref "U1") (pin "V12") (pinfunction "VPP_V12") (pintype "power_in"))
      (node (ref "U1") (pin "V5") (pinfunction "VDDI5_V5") (pintype "passive"))
    )
    (net (code "11") (name "VDD_3V0") (class "Default")
      (node (ref "Cb90") (pin "2") (pinfunction "2_2") (pintype "passive"))
      (node (ref "Cb91") (pin "2") (pinfunction "2_2") (pintype "passive"))
      (node (ref "Cb92") (pin "2") (pinfunction "2_2") (pintype "passive"))
      (node (ref "Cb93") (pin "2") (pinfunction "2_2") (pintype "passive"))
      (node (ref "Cb95") (pin "2") (pinfunction "2_2") (pintype "passive"))
      (node (ref "Cb96") (pin "2") (pinfunction "2_2") (pintype "passive"))
      (node (ref "Cb97") (pin "2") (pinfunction "2_2") (pintype "passive"))
      (node (ref "CbA0") (pin "2") (pinfunction "2_2") (pintype "passive"))
      (node (ref "CbA1") (pin "2") (pinfunction "2_2") (pintype "passive"))
      (node (ref "CbB0") (pin "2") (pinfunction "2_2") (pintype "passive"))
    )
    (net (code "12") (name "unconnected-(U1H-VDDI6-PadAA9)") (class "Default")
      (node (ref "U1") (pin "AA9") (pinfunction "VDDI6_AA9") (pintype "passive+no_connect"))
    )
    (net (code "13") (name "unconnected-(U1H-VDDI6-PadR10)") (class "Default")
      (node (ref "U1") (pin "R10") (pinfunction "VDDI6_R10") (pintype "passive+no_connect"))
    )
    (net (code "14") (name "unconnected-(U1H-VDDI6-PadV9)") (class "Default")
      (node (ref "U1") (pin "V9") (pinfunction "VDDI6_V9") (pintype "passive+no_connect"))
    )
    (net (code "15") (name "unconnected-(U1H-VDDI7-PadW20)") (class "Default")
      (node (ref "U1") (pin "W20") (pinfunction "VDDI7_W20") (pintype "passive+no_connect"))
    )
    (net (code "16") (name "unconnected-(U1H-VDDI8-PadN15)") (class "Default")
      (node (ref "U1") (pin "N15") (pinfunction "VDDI8_N15") (pintype "power_in+no_connect"))
    )
    (net (code "17") (name "unconnected-(U1H-VDDI8-PadR18)") (class "Default")
      (node (ref "U1") (pin "R18") (pinfunction "VDDI8_R18") (pintype "passive+no_connect"))
    )
    (net (code "18") (name "unconnected-(U1H-VDDI9-PadD20)") (class "Default")
      (node (ref "U1") (pin "D20") (pinfunction "VDDI9_D20") (pintype "passive+no_connect"))
    )
    (net (code "19") (name "unconnected-(U1H-VDDI9-PadF17)") (class "Default")
      (node (ref "U1") (pin "F17") (pinfunction "VDDI9_F17") (pintype "passive+no_connect"))
    )
    (net (code "20") (name "unconnected-(U1H-VDDI9-PadJ15)") (class "Default")
      (node (ref "U1") (pin "J15") (pinfunction "VDDI9_J15") (pintype "passive+no_connect"))
    )
    (net (code "21") (name "unconnected-(U1H-VDDI9-PadK20)") (class "Default")
      (node (ref "U1") (pin "K20") (pinfunction "VDDI9_K20") (pintype "passive+no_connect"))
    )
  )
)
